# DfMUX_Power.net
KiCad netlist of a schematic drawn in Altium Designer
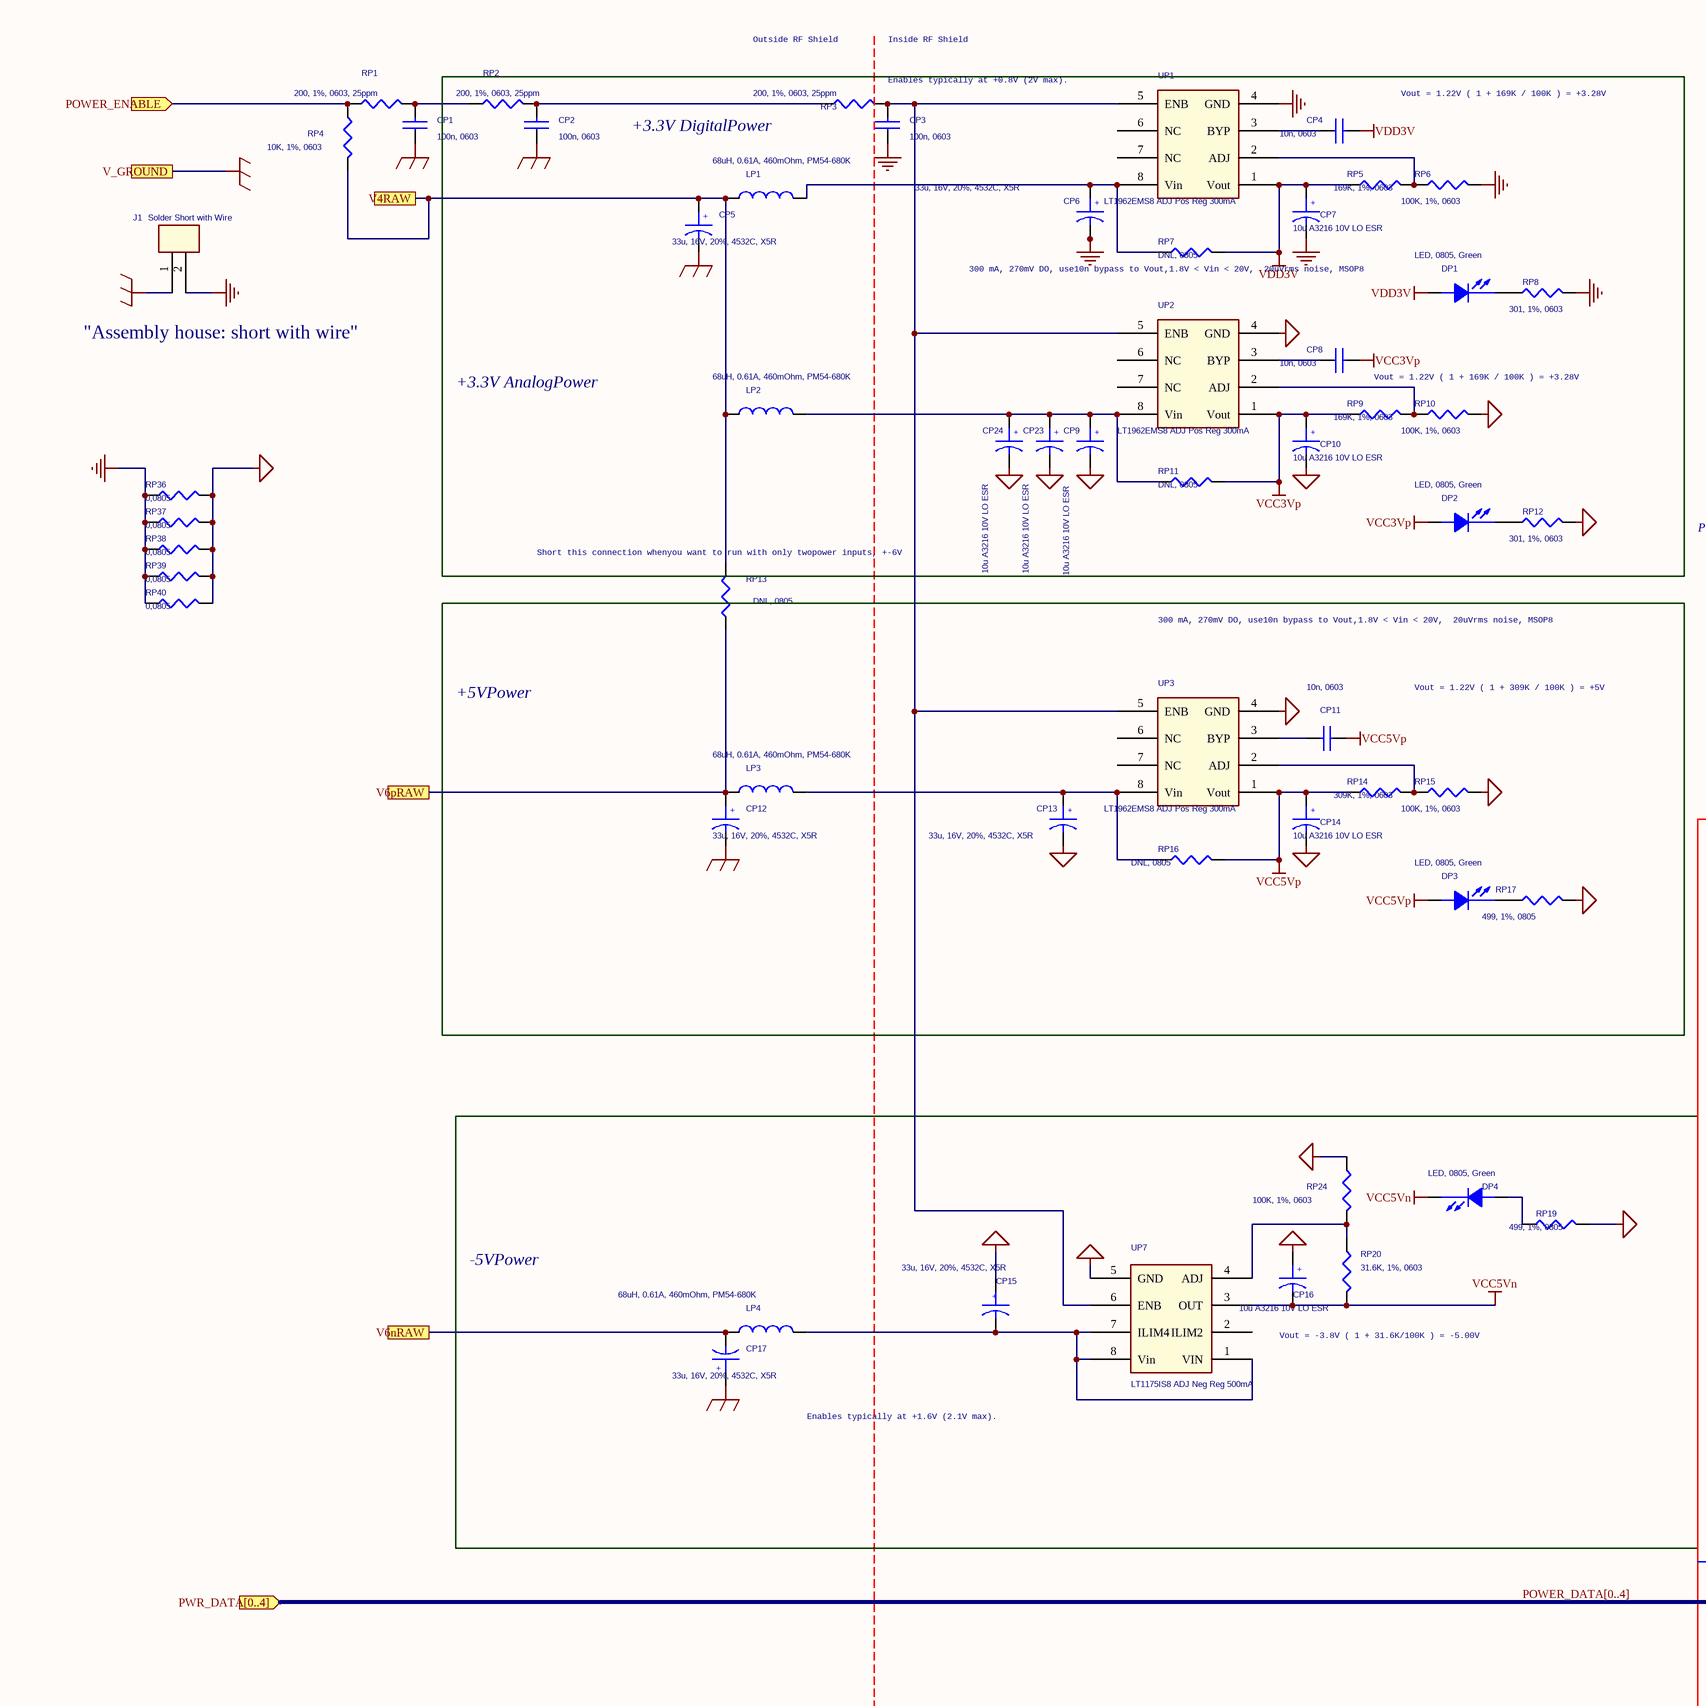
[diagram p0: DfMUX_Power.SchDoc, left]
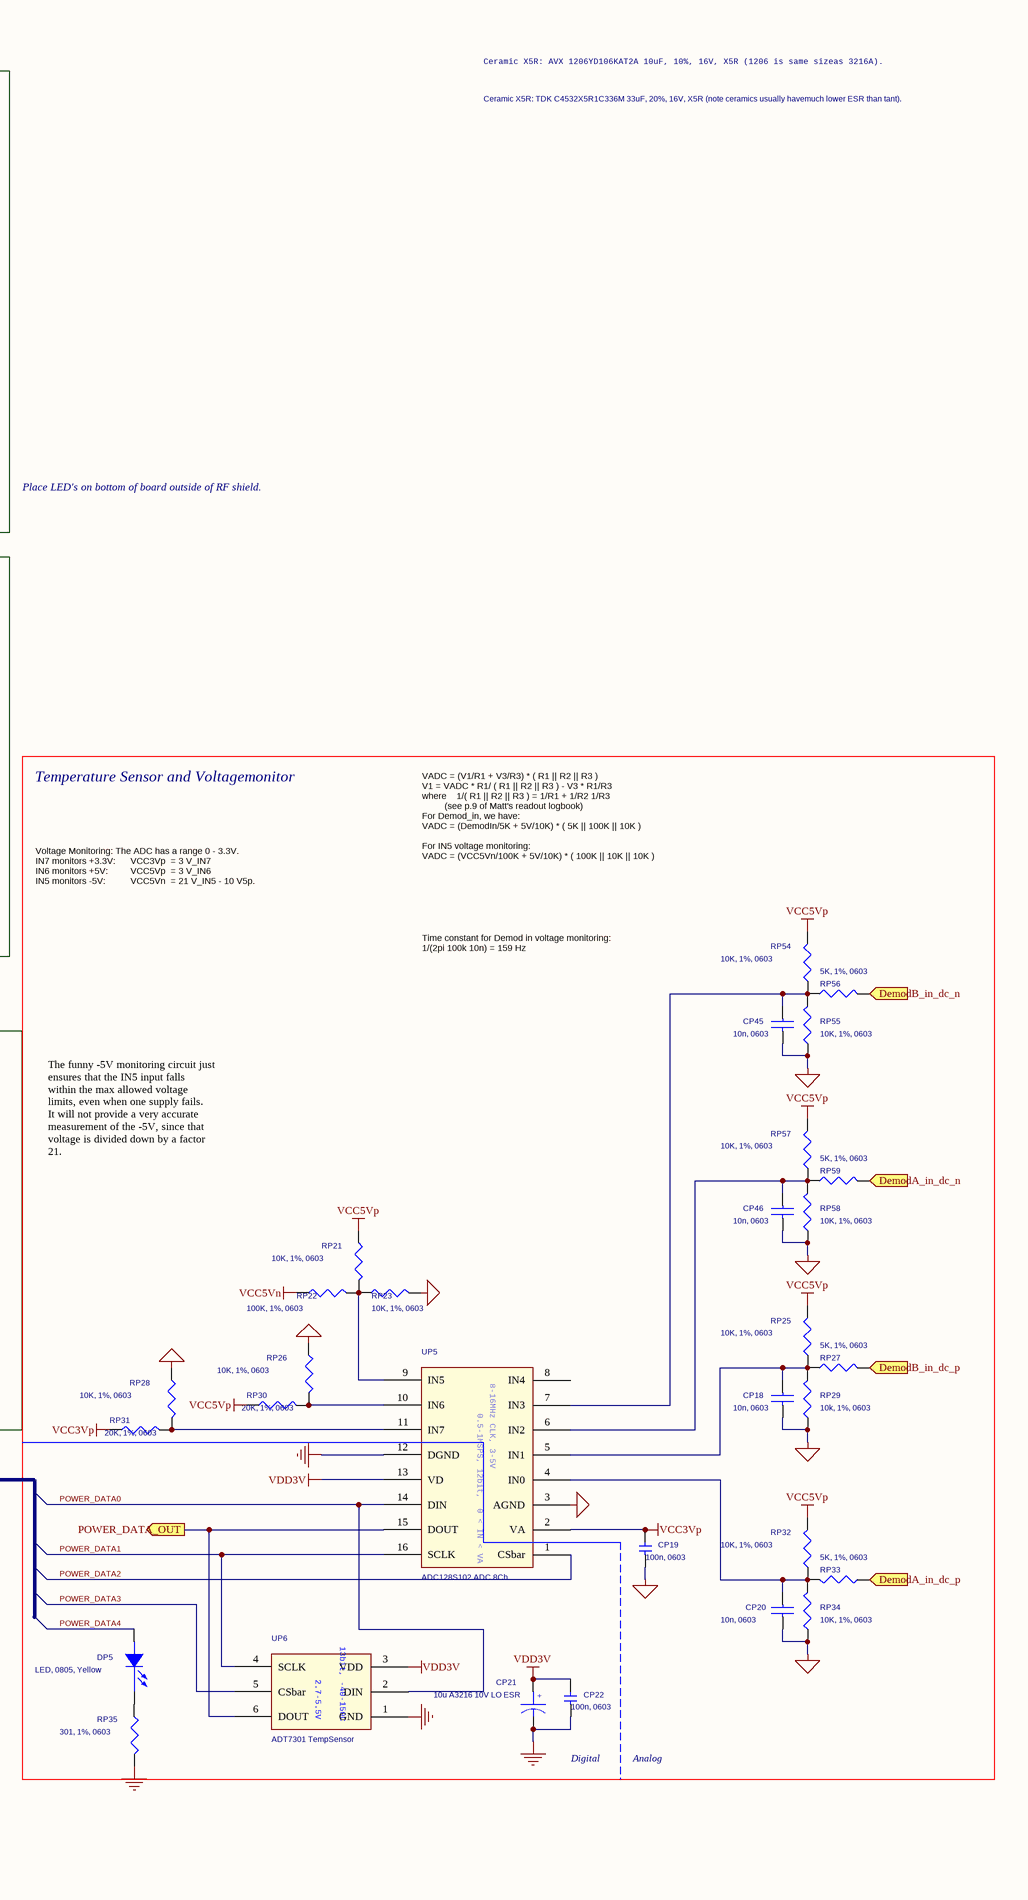
[diagram p1: DfMUX_Power.SchDoc, right]

(export (version "E")
  (design (tool "Eeschema 10.0.6"))
  (components
    (comp (ref "CP1") (value "100n, 0603") (footprint "0603C") (libsource (lib "*") (part "CAP NP")))
    (comp (ref "CP2") (value "100n, 0603") (footprint "0603C") (libsource (lib "*") (part "CAP NP")))
    (comp (ref "CP3") (value "100n, 0603") (footprint "0603C") (libsource (lib "*") (part "CAP NP")))
    (comp (ref "CP4") (value "10n, 0603") (footprint "0603C") (libsource (lib "*") (part "CAP NP")))
    (comp (ref "CP5") (value "33u, 16V, 20%, 4532C, X5R") (libsource (lib "*") (part "CAP_POL")))
    (comp (ref "CP6") (value "33u, 16V, 20%, 4532C, X5R") (libsource (lib "*") (part "CAP_POL")))
    (comp (ref "CP7") (value "10u A3216 10V LO ESR") (libsource (lib "*") (part "CAP_POL")))
    (comp (ref "CP8") (value "10n, 0603") (footprint "0603C") (libsource (lib "*") (part "CAP NP")))
    (comp (ref "CP9") (value "10u A3216 10V LO ESR") (libsource (lib "*") (part "CAP_POL")))
    (comp (ref "CP10") (value "10u A3216 10V LO ESR") (libsource (lib "*") (part "CAP_POL")))
    (comp (ref "CP11") (value "10n, 0603") (footprint "0603C") (libsource (lib "*") (part "CAP NP")))
    (comp (ref "CP12") (value "33u, 16V, 20%, 4532C, X5R") (libsource (lib "*") (part "CAP_POL")))
    (comp (ref "CP13") (value "33u, 16V, 20%, 4532C, X5R") (libsource (lib "*") (part "CAP_POL")))
    (comp (ref "CP14") (value "10u A3216 10V LO ESR") (libsource (lib "*") (part "CAP_POL")))
    (comp (ref "CP15") (value "33u, 16V, 20%, 4532C, X5R") (libsource (lib "") (part "CAP_POL_1")))
    (comp (ref "CP16") (value "10u A3216 10V LO ESR") (libsource (lib "*") (part "CAP_POL")))
    (comp (ref "CP17") (value "33u, 16V, 20%, 4532C, X5R") (libsource (lib "*") (part "CAP_POL")))
    (comp (ref "CP18") (value "10n, 0603") (footprint "0603C") (libsource (lib "*") (part "CAP NP")))
    (comp (ref "CP19") (value "100n, 0603") (footprint "0603C") (libsource (lib "*") (part "C")))
    (comp (ref "CP20") (value "10n, 0603") (footprint "0603C") (libsource (lib "*") (part "CAP NP")))
    (comp (ref "CP21") (value "10u A3216 10V LO ESR") (libsource (lib "*") (part "CAPACITOR POL")))
    (comp (ref "CP22") (value "100n, 0603") (footprint "0603C") (libsource (lib "*") (part "C")))
    (comp (ref "CP23") (value "10u A3216 10V LO ESR") (libsource (lib "*") (part "CAP_POL")))
    (comp (ref "CP24") (value "10u A3216 10V LO ESR") (libsource (lib "*") (part "CAP_POL")))
    (comp (ref "CP45") (value "10n, 0603") (footprint "0603C") (libsource (lib "*") (part "CAP NP")))
    (comp (ref "CP46") (value "10n, 0603") (footprint "0603C") (libsource (lib "*") (part "CAP NP")))
    (comp (ref "DP1") (value "LED, 0805, Green") (libsource (lib "*") (part "LED")))
    (comp (ref "DP2") (value "LED, 0805, Green") (libsource (lib "*") (part "LED")))
    (comp (ref "DP3") (value "LED, 0805, Green") (libsource (lib "*") (part "LED")))
    (comp (ref "DP4") (value "LED, 0805, Green") (libsource (lib "*") (part "LED")))
    (comp (ref "DP5") (value "LED, 0805, Yellow") (libsource (lib "*") (part "LED")))
    (comp (ref "J1") (value "Solder Short with Wire") (libsource (lib "*") (part "CON2")))
    (comp (ref "LP1") (value "68uH, 0.61A, 460mOhm, PM54-680K") (libsource (lib "*") (part "L")))
    (comp (ref "LP2") (value "68uH, 0.61A, 460mOhm, PM54-680K") (libsource (lib "*") (part "L")))
    (comp (ref "LP3") (value "68uH, 0.61A, 460mOhm, PM54-680K") (libsource (lib "*") (part "L")))
    (comp (ref "LP4") (value "68uH, 0.61A, 460mOhm, PM54-680K") (libsource (lib "*") (part "L")))
    (comp (ref "RP1")
      (value "200, 1%, 0603, 25ppm")
      (footprint "0603R")
      (libsource (lib "*") (part "R_Dup1"))
    )
    (comp (ref "RP2")
      (value "200, 1%, 0603, 25ppm")
      (footprint "0603R")
      (libsource (lib "*") (part "R_Dup1"))
    )
    (comp (ref "RP3")
      (value "200, 1%, 0603, 25ppm")
      (footprint "0603R")
      (libsource (lib "*") (part "R_Dup1"))
    )
    (comp (ref "RP4") (value "10K, 1%, 0603") (footprint "0603R") (libsource (lib "*") (part "R_Dup1")))
    (comp (ref "RP5") (value "169K, 1%, 0603") (footprint "0603R") (libsource (lib "*") (part "R")))
    (comp (ref "RP6") (value "100K, 1%, 0603") (footprint "0603R") (libsource (lib "*") (part "R")))
    (comp (ref "RP7") (value "DNL, 0805") (footprint "0805R") (libsource (lib "*") (part "R_Dup1")))
    (comp (ref "RP8") (value "301, 1%, 0603") (footprint "0603R") (libsource (lib "*") (part "R_Dup1")))
    (comp (ref "RP9") (value "169K, 1%, 0603") (footprint "0603R") (libsource (lib "*") (part "R")))
    (comp (ref "RP10") (value "100K, 1%, 0603") (footprint "0603R") (libsource (lib "*") (part "R")))
    (comp (ref "RP11") (value "DNL, 0805") (footprint "0805R") (libsource (lib "*") (part "R_Dup1")))
    (comp (ref "RP12") (value "301, 1%, 0603") (footprint "0603R") (libsource (lib "*") (part "R_Dup1")))
    (comp (ref "RP13") (value "DNL, 0805") (footprint "0805R") (libsource (lib "*") (part "R_Dup1")))
    (comp (ref "RP14") (value "309K, 1%, 0603") (footprint "0603R") (libsource (lib "*") (part "R")))
    (comp (ref "RP15") (value "100K, 1%, 0603") (footprint "0603R") (libsource (lib "*") (part "R")))
    (comp (ref "RP16") (value "DNL, 0805") (footprint "0805R") (libsource (lib "*") (part "R_Dup1")))
    (comp (ref "RP17") (value "499, 1%, 0805") (footprint "0805R") (libsource (lib "*") (part "R_Dup1")))
    (comp (ref "RP19") (value "499, 1%, 0805") (footprint "0805R") (libsource (lib "*") (part "R_Dup1")))
    (comp (ref "RP20") (value "31.6K, 1%, 0603") (footprint "0603R") (libsource (lib "*") (part "R")))
    (comp (ref "RP21") (value "10K, 1%, 0603") (footprint "0603R") (libsource (lib "*") (part "R_Dup1")))
    (comp (ref "RP22") (value "100K, 1%, 0603") (footprint "0603R") (libsource (lib "*") (part "R_Dup1")))
    (comp (ref "RP23") (value "10K, 1%, 0603") (footprint "0603R") (libsource (lib "*") (part "R_Dup1")))
    (comp (ref "RP24") (value "100K, 1%, 0603") (footprint "0603R") (libsource (lib "*") (part "R")))
    (comp (ref "RP25") (value "10K, 1%, 0603") (footprint "0603R") (libsource (lib "*") (part "R_Dup1")))
    (comp (ref "RP26") (value "10K, 1%, 0603") (footprint "0603R") (libsource (lib "*") (part "R_Dup1")))
    (comp (ref "RP27") (value "5K, 1%, 0603") (footprint "0603R") (libsource (lib "*") (part "R_Dup1")))
    (comp (ref "RP28") (value "10K, 1%, 0603") (footprint "0603R") (libsource (lib "*") (part "R_Dup1")))
    (comp (ref "RP29") (value "10k, 1%, 0603") (footprint "0603R") (libsource (lib "*") (part "R_Dup1")))
    (comp (ref "RP30") (value "20K, 1%, 0603") (footprint "0603R") (libsource (lib "*") (part "R_Dup1")))
    (comp (ref "RP31") (value "20K, 1%, 0603") (footprint "0603R") (libsource (lib "*") (part "R_Dup1")))
    (comp (ref "RP32") (value "10K, 1%, 0603") (footprint "0603R") (libsource (lib "*") (part "R_Dup1")))
    (comp (ref "RP33") (value "5K, 1%, 0603") (footprint "0603R") (libsource (lib "*") (part "R_Dup1")))
    (comp (ref "RP34") (value "10K, 1%, 0603") (footprint "0603R") (libsource (lib "*") (part "R_Dup1")))
    (comp (ref "RP35") (value "301, 1%, 0603") (footprint "0603R") (libsource (lib "*") (part "R_Dup1")))
    (comp (ref "RP36") (value "0,0805") (footprint "0805R") (libsource (lib "*") (part "R_Dup1")))
    (comp (ref "RP37") (value "0,0805") (footprint "0805R") (libsource (lib "*") (part "R_Dup1")))
    (comp (ref "RP38") (value "0,0805") (footprint "0805R") (libsource (lib "*") (part "R_Dup1")))
    (comp (ref "RP39") (value "0,0805") (footprint "0805R") (libsource (lib "*") (part "R_Dup1")))
    (comp (ref "RP40") (value "0,0805") (footprint "0805R") (libsource (lib "*") (part "R_Dup1")))
    (comp (ref "RP54") (value "10K, 1%, 0603") (footprint "0603R") (libsource (lib "*") (part "R_Dup1")))
    (comp (ref "RP55") (value "10K, 1%, 0603") (footprint "0603R") (libsource (lib "*") (part "R_Dup1")))
    (comp (ref "RP56") (value "5K, 1%, 0603") (footprint "0603R") (libsource (lib "*") (part "R_Dup1")))
    (comp (ref "RP57") (value "10K, 1%, 0603") (footprint "0603R") (libsource (lib "*") (part "R_Dup1")))
    (comp (ref "RP58") (value "10K, 1%, 0603") (footprint "0603R") (libsource (lib "*") (part "R_Dup1")))
    (comp (ref "RP59") (value "5K, 1%, 0603") (footprint "0603R") (libsource (lib "*") (part "R_Dup1")))
    (comp (ref "UP1") (value "LT1962EMS8 ADJ Pos Reg 300mA") (libsource (lib "*") (part "LT1962EMS8_0_Dup1")))
    (comp (ref "UP2") (value "LT1962EMS8 ADJ Pos Reg 300mA") (libsource (lib "*") (part "LT1962EMS8_0_Dup1")))
    (comp (ref "UP3") (value "LT1962EMS8 ADJ Pos Reg 300mA") (libsource (lib "*") (part "LT1962EMS8_0_Dup1")))
    (comp (ref "UP5")
      (value "ADC128S102 ADC 8Ch")
      (footprint "TSSOP16")
      (libsource (lib "*") (part "ADC128S102 ADC 8Ch"))
    )
    (comp (ref "UP6")
      (value "ADT7301 TempSensor")
      (footprint "SOT23-6")
      (libsource (lib "*") (part "ADT7301 TempSensor"))
    )
    (comp (ref "UP7") (value "LT1175IS8 ADJ Neg Reg 500mA") (libsource (lib "*") (part "LT1962EMS8_5")))
  )
  (nets
    (net (code "1") (name "/DemodA_in_dc_n") (class "Default")
      (node (ref "RP59") (pin "2") (pinfunction "2_2") (pintype "passive"))
    )
    (net (code "2") (name "/DemodA_in_dc_p") (class "Default")
      (node (ref "RP33") (pin "1") (pinfunction "1_1") (pintype "passive"))
    )
    (net (code "3") (name "/DemodB_in_dc_n") (class "Default")
      (node (ref "RP56") (pin "2") (pinfunction "2_2") (pintype "passive"))
    )
    (net (code "4") (name "/DemodB_in_dc_p") (class "Default")
      (node (ref "RP27") (pin "2") (pinfunction "2_2") (pintype "passive"))
    )
    (net (code "5") (name "/POWER_DATA0") (class "Default")
      (node (ref "UP5") (pin "14") (pinfunction "DIN_14") (pintype "passive"))
      (node (ref "UP6") (pin "2") (pinfunction "DIN_2") (pintype "passive"))
    )
    (net (code "6") (name "/POWER_DATA1") (class "Default")
      (node (ref "UP5") (pin "16") (pinfunction "SCLK_16") (pintype "passive"))
      (node (ref "UP6") (pin "4") (pinfunction "SCLK_4") (pintype "passive"))
    )
    (net (code "7") (name "/POWER_DATA2") (class "Default")
      (node (ref "UP5") (pin "1") (pinfunction "CSbar_1") (pintype "passive"))
    )
    (net (code "8") (name "/POWER_DATA3") (class "Default")
      (node (ref "UP6") (pin "5") (pinfunction "CSbar_5") (pintype "passive"))
    )
    (net (code "9") (name "/POWER_DATA4") (class "Default")
      (node (ref "DP5") (pin "1") (pinfunction "ANODE_1") (pintype "passive"))
    )
    (net (code "11") (name "/POWER_DATA_OUT") (class "Default")
      (node (ref "UP5") (pin "15") (pinfunction "DOUT_15") (pintype "passive"))
      (node (ref "UP6") (pin "6") (pinfunction "DOUT_6") (pintype "passive"))
    )
    (net (code "12") (name "/POWER_ENABLE") (class "Default")
      (node (ref "RP1") (pin "1") (pinfunction "1_1") (pintype "passive"))
      (node (ref "RP4") (pin "1") (pinfunction "1_1") (pintype "passive"))
    )
    (net (code "13") (name "/V4RAW") (class "Default")
      (node (ref "CP5") (pin "1") (pinfunction "1_1") (pintype "passive"))
      (node (ref "LP1") (pin "1") (pinfunction "1_1") (pintype "passive"))
      (node (ref "LP2") (pin "1") (pinfunction "1_1") (pintype "passive"))
      (node (ref "RP13") (pin "2") (pinfunction "2_2") (pintype "passive"))
      (node (ref "RP4") (pin "2") (pinfunction "2_2") (pintype "passive"))
    )
    (net (code "14") (name "/V6nRAW") (class "Default")
      (node (ref "CP17") (pin "2") (pinfunction "2_2") (pintype "passive"))
      (node (ref "LP4") (pin "1") (pinfunction "1_1") (pintype "passive"))
    )
    (net (code "15") (name "/V6pRAW") (class "Default")
      (node (ref "CP12") (pin "1") (pinfunction "1_1") (pintype "passive"))
      (node (ref "LP3") (pin "1") (pinfunction "1_1") (pintype "passive"))
      (node (ref "RP13") (pin "1") (pinfunction "1_1") (pintype "passive"))
    )
    (net (code "16") (name "GND_DIG") (class "Default")
      (node (ref "CP21") (pin "2") (pinfunction "2_2") (pintype "passive"))
      (node (ref "CP22") (pin "1") (pinfunction "1_1") (pintype "passive"))
      (node (ref "CP3") (pin "1") (pinfunction "1_1") (pintype "passive"))
      (node (ref "CP6") (pin "2") (pinfunction "2_2") (pintype "passive"))
      (node (ref "CP7") (pin "2") (pinfunction "2_2") (pintype "passive"))
      (node (ref "J1") (pin "2") (pinfunction "2_2") (pintype "passive"))
      (node (ref "RP35") (pin "2") (pinfunction "2_2") (pintype "passive"))
      (node (ref "RP36") (pin "1") (pinfunction "1_1") (pintype "passive"))
      (node (ref "RP37") (pin "1") (pinfunction "1_1") (pintype "passive"))
      (node (ref "RP38") (pin "1") (pinfunction "1_1") (pintype "passive"))
      (node (ref "RP39") (pin "1") (pinfunction "1_1") (pintype "passive"))
      (node (ref "RP40") (pin "1") (pinfunction "1_1") (pintype "passive"))
      (node (ref "RP6") (pin "2") (pinfunction "2_2") (pintype "passive"))
      (node (ref "RP8") (pin "2") (pinfunction "2_2") (pintype "passive"))
      (node (ref "UP1") (pin "4") (pinfunction "GND_4") (pintype "passive"))
      (node (ref "UP5") (pin "12") (pinfunction "DGND_12") (pintype "passive"))
      (node (ref "UP6") (pin "1") (pinfunction "GND_1") (pintype "passive"))
    )
    (net (code "17") (name "GND_EARTH") (class "Default")
      (node (ref "CP1") (pin "1") (pinfunction "1_1") (pintype "passive"))
      (node (ref "CP12") (pin "2") (pinfunction "2_2") (pintype "passive"))
      (node (ref "CP17") (pin "1") (pinfunction "1_1") (pintype "passive"))
      (node (ref "CP2") (pin "1") (pinfunction "1_1") (pintype "passive"))
      (node (ref "CP5") (pin "2") (pinfunction "2_2") (pintype "passive"))
      (node (ref "J1") (pin "1") (pinfunction "1_1") (pintype "passive"))
    )
    (net (code "18") (name "GND_SIGNAL") (class "Default")
      (node (ref "CP10") (pin "2") (pinfunction "2_2") (pintype "passive"))
      (node (ref "CP13") (pin "2") (pinfunction "2_2") (pintype "passive"))
      (node (ref "CP14") (pin "2") (pinfunction "2_2") (pintype "passive"))
      (node (ref "CP15") (pin "1") (pinfunction "1_1") (pintype "passive"))
      (node (ref "CP16") (pin "1") (pinfunction "1_1") (pintype "passive"))
      (node (ref "CP18") (pin "2") (pinfunction "2_2") (pintype "passive"))
      (node (ref "CP19") (pin "1") (pinfunction "1_1") (pintype "passive"))
      (node (ref "CP20") (pin "2") (pinfunction "2_2") (pintype "passive"))
      (node (ref "CP23") (pin "2") (pinfunction "2_2") (pintype "passive"))
      (node (ref "CP24") (pin "2") (pinfunction "2_2") (pintype "passive"))
      (node (ref "CP45") (pin "2") (pinfunction "2_2") (pintype "passive"))
      (node (ref "CP46") (pin "2") (pinfunction "2_2") (pintype "passive"))
      (node (ref "CP9") (pin "2") (pinfunction "2_2") (pintype "passive"))
      (node (ref "RP10") (pin "2") (pinfunction "2_2") (pintype "passive"))
      (node (ref "RP12") (pin "2") (pinfunction "2_2") (pintype "passive"))
      (node (ref "RP15") (pin "2") (pinfunction "2_2") (pintype "passive"))
      (node (ref "RP17") (pin "2") (pinfunction "2_2") (pintype "passive"))
      (node (ref "RP19") (pin "2") (pinfunction "2_2") (pintype "passive"))
      (node (ref "RP23") (pin "2") (pinfunction "2_2") (pintype "passive"))
      (node (ref "RP24") (pin "1") (pinfunction "1_1") (pintype "passive"))
      (node (ref "RP26") (pin "1") (pinfunction "1_1") (pintype "passive"))
      (node (ref "RP28") (pin "1") (pinfunction "1_1") (pintype "passive"))
      (node (ref "RP29") (pin "1") (pinfunction "1_1") (pintype "passive"))
      (node (ref "RP34") (pin "1") (pinfunction "1_1") (pintype "passive"))
      (node (ref "RP36") (pin "2") (pinfunction "2_2") (pintype "passive"))
      (node (ref "RP37") (pin "2") (pinfunction "2_2") (pintype "passive"))
      (node (ref "RP38") (pin "2") (pinfunction "2_2") (pintype "passive"))
      (node (ref "RP39") (pin "2") (pinfunction "2_2") (pintype "passive"))
      (node (ref "RP40") (pin "2") (pinfunction "2_2") (pintype "passive"))
      (node (ref "RP55") (pin "1") (pinfunction "1_1") (pintype "passive"))
      (node (ref "RP58") (pin "1") (pinfunction "1_1") (pintype "passive"))
      (node (ref "UP2") (pin "4") (pinfunction "GND_4") (pintype "passive"))
      (node (ref "UP3") (pin "4") (pinfunction "GND_4") (pintype "passive"))
      (node (ref "UP5") (pin "3") (pinfunction "AGND_3") (pintype "passive"))
      (node (ref "UP7") (pin "5") (pinfunction "GND_5") (pintype "passive"))
    )
    (net (code "19") (name "Net-(CP1-Pad2)") (class "Default")
      (node (ref "CP1") (pin "2") (pinfunction "2_2") (pintype "passive"))
      (node (ref "RP1") (pin "2") (pinfunction "2_2") (pintype "passive"))
      (node (ref "RP2") (pin "1") (pinfunction "1_1") (pintype "passive"))
    )
    (net (code "20") (name "Net-(CP2-Pad2)") (class "Default")
      (node (ref "CP2") (pin "2") (pinfunction "2_2") (pintype "passive"))
      (node (ref "RP2") (pin "2") (pinfunction "2_2") (pintype "passive"))
      (node (ref "RP3") (pin "1") (pinfunction "1_1") (pintype "passive"))
    )
    (net (code "21") (name "Net-(DP1-CATHODE)") (class "Default")
      (node (ref "DP1") (pin "2") (pinfunction "CATHODE_2") (pintype "passive"))
      (node (ref "RP8") (pin "1") (pinfunction "1_1") (pintype "passive"))
    )
    (net (code "22") (name "Net-(DP2-CATHODE)") (class "Default")
      (node (ref "DP2") (pin "2") (pinfunction "CATHODE_2") (pintype "passive"))
      (node (ref "RP12") (pin "1") (pinfunction "1_1") (pintype "passive"))
    )
    (net (code "23") (name "Net-(DP3-CATHODE)") (class "Default")
      (node (ref "DP3") (pin "2") (pinfunction "CATHODE_2") (pintype "passive"))
      (node (ref "RP17") (pin "1") (pinfunction "1_1") (pintype "passive"))
    )
    (net (code "24") (name "Net-(DP4-ANODE)") (class "Default")
      (node (ref "DP4") (pin "1") (pinfunction "ANODE_1") (pintype "passive"))
      (node (ref "RP19") (pin "1") (pinfunction "1_1") (pintype "passive"))
    )
    (net (code "25") (name "Net-(DP5-CATHODE)") (class "Default")
      (node (ref "DP5") (pin "2") (pinfunction "CATHODE_2") (pintype "passive"))
      (node (ref "RP35") (pin "1") (pinfunction "1_1") (pintype "passive"))
    )
    (net (code "26") (name "Net-(UP1-ADJ)") (class "Default")
      (node (ref "RP5") (pin "2") (pinfunction "2_2") (pintype "passive"))
      (node (ref "RP6") (pin "1") (pinfunction "1_1") (pintype "passive"))
      (node (ref "UP1") (pin "2") (pinfunction "ADJ_2") (pintype "passive"))
    )
    (net (code "27") (name "Net-(UP1-BYP)") (class "Default")
      (node (ref "CP4") (pin "1") (pinfunction "1_1") (pintype "passive"))
      (node (ref "UP1") (pin "3") (pinfunction "BYP_3") (pintype "passive"))
    )
    (net (code "28") (name "Net-(UP1-ENB)") (class "Default")
      (node (ref "CP3") (pin "2") (pinfunction "2_2") (pintype "passive"))
      (node (ref "RP3") (pin "2") (pinfunction "2_2") (pintype "passive"))
      (node (ref "UP1") (pin "5") (pinfunction "ENB_5") (pintype "passive"))
      (node (ref "UP2") (pin "5") (pinfunction "ENB_5") (pintype "passive"))
      (node (ref "UP3") (pin "5") (pinfunction "ENB_5") (pintype "passive"))
      (node (ref "UP7") (pin "6") (pinfunction "ENB_6") (pintype "passive"))
    )
    (net (code "29") (name "Net-(UP1-Vin)") (class "Default")
      (node (ref "CP6") (pin "1") (pinfunction "1_1") (pintype "passive"))
      (node (ref "LP1") (pin "2") (pinfunction "2_2") (pintype "passive"))
      (node (ref "RP7") (pin "1") (pinfunction "1_1") (pintype "passive"))
      (node (ref "UP1") (pin "8") (pinfunction "Vin_8") (pintype "passive"))
    )
    (net (code "30") (name "Net-(UP2-ADJ)") (class "Default")
      (node (ref "RP10") (pin "1") (pinfunction "1_1") (pintype "passive"))
      (node (ref "RP9") (pin "2") (pinfunction "2_2") (pintype "passive"))
      (node (ref "UP2") (pin "2") (pinfunction "ADJ_2") (pintype "passive"))
    )
    (net (code "31") (name "Net-(UP2-BYP)") (class "Default")
      (node (ref "CP8") (pin "1") (pinfunction "1_1") (pintype "passive"))
      (node (ref "UP2") (pin "3") (pinfunction "BYP_3") (pintype "passive"))
    )
    (net (code "32") (name "Net-(UP2-Vin)") (class "Default")
      (node (ref "CP23") (pin "1") (pinfunction "1_1") (pintype "passive"))
      (node (ref "CP24") (pin "1") (pinfunction "1_1") (pintype "passive"))
      (node (ref "CP9") (pin "1") (pinfunction "1_1") (pintype "passive"))
      (node (ref "LP2") (pin "2") (pinfunction "2_2") (pintype "passive"))
      (node (ref "RP11") (pin "1") (pinfunction "1_1") (pintype "passive"))
      (node (ref "UP2") (pin "8") (pinfunction "Vin_8") (pintype "passive"))
    )
    (net (code "33") (name "Net-(UP3-ADJ)") (class "Default")
      (node (ref "RP14") (pin "2") (pinfunction "2_2") (pintype "passive"))
      (node (ref "RP15") (pin "1") (pinfunction "1_1") (pintype "passive"))
      (node (ref "UP3") (pin "2") (pinfunction "ADJ_2") (pintype "passive"))
    )
    (net (code "34") (name "Net-(UP3-BYP)") (class "Default")
      (node (ref "CP11") (pin "2") (pinfunction "2_2") (pintype "passive"))
      (node (ref "UP3") (pin "3") (pinfunction "BYP_3") (pintype "passive"))
    )
    (net (code "35") (name "Net-(UP3-Vin)") (class "Default")
      (node (ref "CP13") (pin "1") (pinfunction "1_1") (pintype "passive"))
      (node (ref "LP3") (pin "2") (pinfunction "2_2") (pintype "passive"))
      (node (ref "RP16") (pin "1") (pinfunction "1_1") (pintype "passive"))
      (node (ref "UP3") (pin "8") (pinfunction "Vin_8") (pintype "passive"))
    )
    (net (code "36") (name "Net-(UP5-IN0)") (class "Default")
      (node (ref "CP20") (pin "1") (pinfunction "1_1") (pintype "passive"))
      (node (ref "RP32") (pin "1") (pinfunction "1_1") (pintype "passive"))
      (node (ref "RP33") (pin "2") (pinfunction "2_2") (pintype "passive"))
      (node (ref "RP34") (pin "2") (pinfunction "2_2") (pintype "passive"))
      (node (ref "UP5") (pin "4") (pinfunction "IN0_4") (pintype "passive"))
    )
    (net (code "37") (name "Net-(UP5-IN1)") (class "Default")
      (node (ref "CP18") (pin "1") (pinfunction "1_1") (pintype "passive"))
      (node (ref "RP25") (pin "1") (pinfunction "1_1") (pintype "passive"))
      (node (ref "RP27") (pin "1") (pinfunction "1_1") (pintype "passive"))
      (node (ref "RP29") (pin "2") (pinfunction "2_2") (pintype "passive"))
      (node (ref "UP5") (pin "5") (pinfunction "IN1_5") (pintype "passive"))
    )
    (net (code "38") (name "Net-(UP5-IN2)") (class "Default")
      (node (ref "CP46") (pin "1") (pinfunction "1_1") (pintype "passive"))
      (node (ref "RP57") (pin "1") (pinfunction "1_1") (pintype "passive"))
      (node (ref "RP58") (pin "2") (pinfunction "2_2") (pintype "passive"))
      (node (ref "RP59") (pin "1") (pinfunction "1_1") (pintype "passive"))
      (node (ref "UP5") (pin "6") (pinfunction "IN2_6") (pintype "passive"))
    )
    (net (code "39") (name "Net-(UP5-IN3)") (class "Default")
      (node (ref "CP45") (pin "1") (pinfunction "1_1") (pintype "passive"))
      (node (ref "RP54") (pin "1") (pinfunction "1_1") (pintype "passive"))
      (node (ref "RP55") (pin "2") (pinfunction "2_2") (pintype "passive"))
      (node (ref "RP56") (pin "1") (pinfunction "1_1") (pintype "passive"))
      (node (ref "UP5") (pin "7") (pinfunction "IN3_7") (pintype "passive"))
    )
    (net (code "40") (name "Net-(UP5-IN5)") (class "Default")
      (node (ref "RP21") (pin "2") (pinfunction "2_2") (pintype "passive"))
      (node (ref "RP22") (pin "2") (pinfunction "2_2") (pintype "passive"))
      (node (ref "RP23") (pin "1") (pinfunction "1_1") (pintype "passive"))
      (node (ref "UP5") (pin "9") (pinfunction "IN5_9") (pintype "passive"))
    )
    (net (code "41") (name "Net-(UP5-IN6)") (class "Default")
      (node (ref "RP26") (pin "2") (pinfunction "2_2") (pintype "passive"))
      (node (ref "RP30") (pin "2") (pinfunction "2_2") (pintype "passive"))
      (node (ref "UP5") (pin "10") (pinfunction "IN6_10") (pintype "passive"))
    )
    (net (code "42") (name "Net-(UP5-IN7)") (class "Default")
      (node (ref "RP28") (pin "2") (pinfunction "2_2") (pintype "passive"))
      (node (ref "RP31") (pin "2") (pinfunction "2_2") (pintype "passive"))
      (node (ref "UP5") (pin "11") (pinfunction "IN7_11") (pintype "passive"))
    )
    (net (code "43") (name "Net-(UP7-ADJ)") (class "Default")
      (node (ref "RP20") (pin "1") (pinfunction "1_1") (pintype "passive"))
      (node (ref "RP24") (pin "2") (pinfunction "2_2") (pintype "passive"))
      (node (ref "UP7") (pin "4") (pinfunction "ADJ_4") (pintype "passive"))
    )
    (net (code "44") (name "Net-(UP7-ILIM4)") (class "Default")
      (node (ref "CP15") (pin "2") (pinfunction "2_2") (pintype "passive"))
      (node (ref "LP4") (pin "2") (pinfunction "2_2") (pintype "passive"))
      (node (ref "UP7") (pin "1") (pinfunction "VIN_1") (pintype "passive"))
      (node (ref "UP7") (pin "7") (pinfunction "ILIM4_7") (pintype "passive"))
      (node (ref "UP7") (pin "8") (pinfunction "Vin_8") (pintype "passive"))
    )
    (net (code "45") (name "VCC3Vp") (class "Default")
      (node (ref "CP10") (pin "1") (pinfunction "1_1") (pintype "passive"))
      (node (ref "CP19") (pin "2") (pinfunction "2_2") (pintype "passive"))
      (node (ref "CP8") (pin "2") (pinfunction "2_2") (pintype "passive"))
      (node (ref "DP2") (pin "1") (pinfunction "ANODE_1") (pintype "passive"))
      (node (ref "RP11") (pin "2") (pinfunction "2_2") (pintype "passive"))
      (node (ref "RP31") (pin "1") (pinfunction "1_1") (pintype "passive"))
      (node (ref "RP9") (pin "1") (pinfunction "1_1") (pintype "passive"))
      (node (ref "UP2") (pin "1") (pinfunction "Vout_1") (pintype "passive"))
      (node (ref "UP5") (pin "2") (pinfunction "VA_2") (pintype "passive"))
    )
    (net (code "46") (name "VCC5Vn") (class "Default")
      (node (ref "CP16") (pin "2") (pinfunction "2_2") (pintype "passive"))
      (node (ref "DP4") (pin "2") (pinfunction "CATHODE_2") (pintype "passive"))
      (node (ref "RP20") (pin "2") (pinfunction "2_2") (pintype "passive"))
      (node (ref "RP22") (pin "1") (pinfunction "1_1") (pintype "passive"))
      (node (ref "UP7") (pin "3") (pinfunction "OUT_3") (pintype "passive"))
    )
    (net (code "47") (name "VCC5Vp") (class "Default")
      (node (ref "CP11") (pin "1") (pinfunction "1_1") (pintype "passive"))
      (node (ref "CP14") (pin "1") (pinfunction "1_1") (pintype "passive"))
      (node (ref "DP3") (pin "1") (pinfunction "ANODE_1") (pintype "passive"))
      (node (ref "RP14") (pin "1") (pinfunction "1_1") (pintype "passive"))
      (node (ref "RP16") (pin "2") (pinfunction "2_2") (pintype "passive"))
      (node (ref "RP21") (pin "1") (pinfunction "1_1") (pintype "passive"))
      (node (ref "RP25") (pin "2") (pinfunction "2_2") (pintype "passive"))
      (node (ref "RP30") (pin "1") (pinfunction "1_1") (pintype "passive"))
      (node (ref "RP32") (pin "2") (pinfunction "2_2") (pintype "passive"))
      (node (ref "RP54") (pin "2") (pinfunction "2_2") (pintype "passive"))
      (node (ref "RP57") (pin "2") (pinfunction "2_2") (pintype "passive"))
      (node (ref "UP3") (pin "1") (pinfunction "Vout_1") (pintype "passive"))
    )
    (net (code "48") (name "VDD3V") (class "Default")
      (node (ref "CP21") (pin "1") (pinfunction "1_1") (pintype "passive"))
      (node (ref "CP22") (pin "2") (pinfunction "2_2") (pintype "passive"))
      (node (ref "CP4") (pin "2") (pinfunction "2_2") (pintype "passive"))
      (node (ref "CP7") (pin "1") (pinfunction "1_1") (pintype "passive"))
      (node (ref "DP1") (pin "1") (pinfunction "ANODE_1") (pintype "passive"))
      (node (ref "RP5") (pin "1") (pinfunction "1_1") (pintype "passive"))
      (node (ref "RP7") (pin "2") (pinfunction "2_2") (pintype "passive"))
      (node (ref "UP1") (pin "1") (pinfunction "Vout_1") (pintype "passive"))
      (node (ref "UP5") (pin "13") (pinfunction "VD_13") (pintype "passive"))
      (node (ref "UP6") (pin "3") (pinfunction "VDD_3") (pintype "passive"))
    )
    (net (code "49") (name "unconnected-(UP1-NC-Pad6)") (class "Default")
      (node (ref "UP1") (pin "6") (pinfunction "NC_6") (pintype "passive"))
    )
    (net (code "50") (name "unconnected-(UP1-NC-Pad7)") (class "Default")
      (node (ref "UP1") (pin "7") (pinfunction "NC_7") (pintype "passive"))
    )
    (net (code "51") (name "unconnected-(UP2-NC-Pad6)") (class "Default")
      (node (ref "UP2") (pin "6") (pinfunction "NC_6") (pintype "passive"))
    )
    (net (code "52") (name "unconnected-(UP2-NC-Pad7)") (class "Default")
      (node (ref "UP2") (pin "7") (pinfunction "NC_7") (pintype "passive"))
    )
    (net (code "53") (name "unconnected-(UP3-NC-Pad6)") (class "Default")
      (node (ref "UP3") (pin "6") (pinfunction "NC_6") (pintype "passive"))
    )
    (net (code "54") (name "unconnected-(UP3-NC-Pad7)") (class "Default")
      (node (ref "UP3") (pin "7") (pinfunction "NC_7") (pintype "passive"))
    )
    (net (code "55") (name "unconnected-(UP5-IN4-Pad8)") (class "Default")
      (node (ref "UP5") (pin "8") (pinfunction "IN4_8") (pintype "passive"))
    )
    (net (code "56") (name "unconnected-(UP7-ILIM2-Pad2)") (class "Default")
      (node (ref "UP7") (pin "2") (pinfunction "ILIM2_2") (pintype "passive"))
    )
  )
)
